# Laser_V-I_Transform.net
KiCad netlist of a schematic drawn in Altium Designer
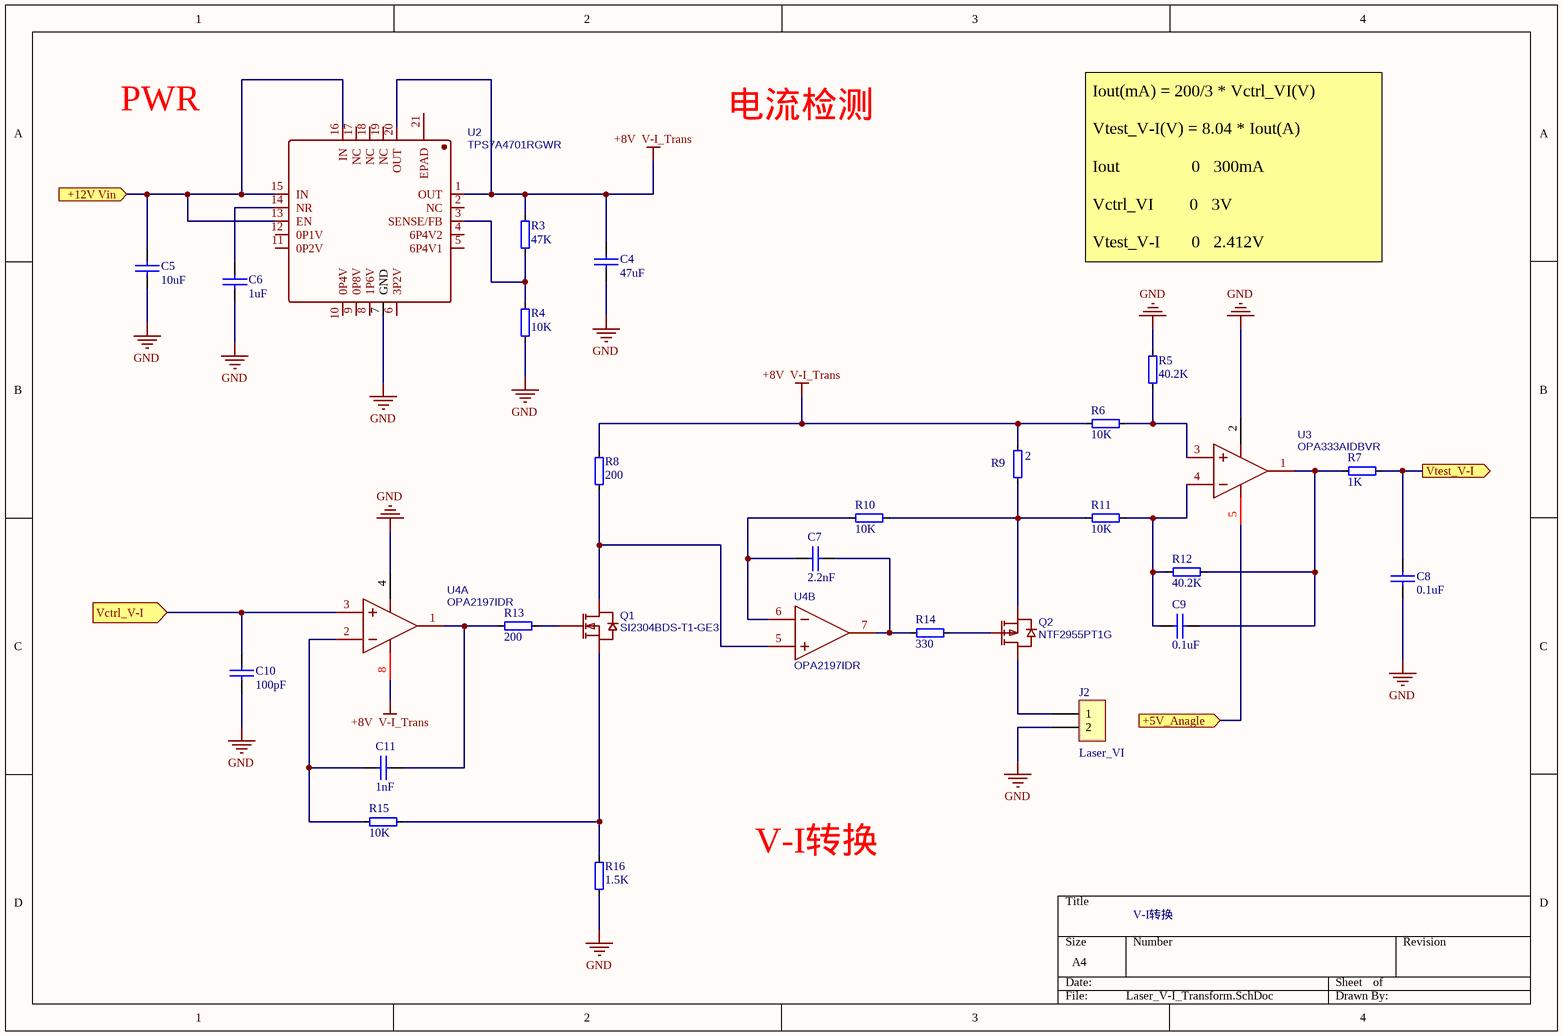
[diagram p0: Laser_V-I_Transform.SchDoc]

(export (version "E")
  (design (tool "Eeschema 10.0.6"))
  (components
    (comp (ref "C4")
      (value "47uF")
      (footprint "C 0603_M")
      (description "Capacitor")
      (libsource (lib "Laser Controller") (part "普通电容"))
    )
    (comp (ref "C5")
      (value "10uF")
      (footprint "C 0603_M")
      (description "Capacitor")
      (libsource (lib "Laser Controller") (part "普通电容"))
    )
    (comp (ref "C6")
      (value "1uF")
      (footprint "C 0603_M")
      (description "Capacitor")
      (libsource (lib "Laser Controller") (part "普通电容"))
    )
    (comp (ref "C7")
      (value "2.2nF")
      (footprint "C 0603_M")
      (description "Capacitor")
      (libsource (lib "Laser Controller") (part "普通电容"))
    )
    (comp (ref "C8")
      (value "0.1uF")
      (footprint "C 0603_M")
      (description "Capacitor")
      (libsource (lib "Laser Controller") (part "普通电容"))
    )
    (comp (ref "C9")
      (value "0.1uF")
      (footprint "C 0603_M")
      (description "Capacitor")
      (libsource (lib "Laser Controller") (part "普通电容"))
    )
    (comp (ref "C10")
      (value "100pF")
      (footprint "C 0603_M")
      (description "Capacitor")
      (libsource (lib "Laser Controller") (part "普通电容"))
    )
    (comp (ref "C11")
      (value "1nF")
      (footprint "C 0603_M")
      (description "Capacitor")
      (libsource (lib "Laser Controller") (part "普通电容"))
    )
    (comp (ref "J2")
      (value "Laser_VI")
      (footprint "KF128-5.08-2P")
      (description "jointbar")
      (libsource (lib "Laser Controller") (part "SIP2"))
    )
    (comp (ref "Q1")
      (value "SI2304BDS-T1-GE3")
      (footprint "SOT-23_L2.9-W1.3-P1.90-LS2.4-BR")
      (fields (field (name "BOM_SUPPLIER PART") "C81446"))
      (libsource (lib "Laser Controller") (part "SI2304BDS-T1-GE3"))
    )
    (comp (ref "Q2")
      (value "NTF2955PT1G")
      (footprint "SOT-223-4_L6.5-W3.5-P2.30-LS7.0-BR")
      (fields (field (name "BOM_SUPPLIER PART") "C710036") (field (name "CONTRIBUTOR") "LCSC"))
      (libsource (lib "Laser Controller") (part "NTF2955PT1G"))
    )
    (comp (ref "R3")
      (value "47K")
      (footprint "0603R")
      (description "电阻精度为0.1%")
      (libsource (lib "Laser Controller") (part "普通电阻"))
    )
    (comp (ref "R4")
      (value "10K")
      (footprint "0603R")
      (description "电阻精度为0.1%")
      (libsource (lib "Laser Controller") (part "普通电阻"))
    )
    (comp (ref "R5") (value "40.2K") (footprint "0603R") (libsource (lib "Laser Controller") (part "普通电阻")))
    (comp (ref "R6") (value "10K") (footprint "0603R") (libsource (lib "Laser Controller") (part "普通电阻")))
    (comp (ref "R7") (value "1K") (footprint "0603R") (libsource (lib "Laser Controller") (part "普通电阻")))
    (comp (ref "R8")
      (value "200")
      (footprint "0603R")
      (description "电阻精度为0.1%")
      (libsource (lib "Laser Controller") (part "普通电阻"))
    )
    (comp (ref "R9")
      (value "2")
      (footprint "0603R")
      (description "采样电阻，电阻精度为0.1%")
      (libsource (lib "Laser Controller") (part "采样电阻"))
    )
    (comp (ref "R10") (value "10K") (footprint "0603R") (libsource (lib "Laser Controller") (part "普通电阻")))
    (comp (ref "R11") (value "10K") (footprint "0603R") (libsource (lib "Laser Controller") (part "普通电阻")))
    (comp (ref "R12") (value "40.2K") (footprint "0603R") (libsource (lib "Laser Controller") (part "普通电阻")))
    (comp (ref "R13") (value "200") (footprint "0603R") (libsource (lib "Laser Controller") (part "普通电阻")))
    (comp (ref "R14") (value "330") (footprint "0603R") (libsource (lib "Laser Controller") (part "普通电阻")))
    (comp (ref "R15") (value "10K") (footprint "0603R") (libsource (lib "Laser Controller") (part "普通电阻")))
    (comp (ref "R16")
      (value "1.5K")
      (footprint "0603R")
      (description "电阻精度为0.1%")
      (libsource (lib "Laser Controller") (part "普通电阻"))
    )
    (comp (ref "U2")
      (value "TPS7A4701RGWR")
      (footprint "VQFN-20_L5.0-W5.0-P0.65-TL-EP")
      (fields (field (name "BOM_SUPPLIER PART") "C90084") (field (name "CONTRIBUTOR") "LCSC"))
      (libsource (lib "Laser Controller") (part "TPS7A4701RGWR"))
    )
    (comp (ref "U3")
      (value "OPA333AIDBVR")
      (footprint "SOT-23-5_L3.0-W1.7-P0.95-LS2.8-BR")
      (fields (field (name "BOM_SUPPLIER PART") "C30878") (field (name "CONTRIBUTOR") "LCSC"))
      (libsource (lib "Laser Controller") (part "OPA333AIDBVR"))
    )
    (comp (ref "U4")
      (value "OPA2197IDR")
      (footprint "SOIC-8_L4.9-W3.9-P1.27-LS6.0-BL")
      (fields (field (name "BOM_SUPPLIER PART") "C139363") (field (name "CONTRIBUTOR") "LCSC"))
      (libsource (lib "Laser Controller") (part "OPA2197IDR"))
    )
  )
  (nets
    (net (code "1") (name "+8V  V-I_Trans") (class "Default")
      (node (ref "C4") (pin "2") (pinfunction "2_2") (pintype "passive"))
      (node (ref "R3") (pin "2") (pinfunction "2_2") (pintype "passive"))
      (node (ref "R6") (pin "1") (pinfunction "1_1") (pintype "passive"))
      (node (ref "R8") (pin "1") (pinfunction "1_1") (pintype "passive"))
      (node (ref "R9") (pin "1") (pinfunction "1_1") (pintype "passive"))
      (node (ref "U2") (pin "1") (pinfunction "OUT_1") (pintype "passive"))
      (node (ref "U2") (pin "20") (pinfunction "OUT_20") (pintype "passive"))
      (node (ref "U4") (pin "8") (pinfunction "V+_8") (pintype "passive"))
    )
    (net (code "2") (name "/+5V_Anagle") (class "Default")
      (node (ref "U3") (pin "5") (pinfunction "V+_5") (pintype "passive"))
    )
    (net (code "3") (name "/+12V Vin") (class "Default")
      (node (ref "C5") (pin "1") (pinfunction "1_1") (pintype "passive"))
      (node (ref "U2") (pin "13") (pinfunction "EN_13") (pintype "passive"))
      (node (ref "U2") (pin "15") (pinfunction "IN_15") (pintype "passive"))
      (node (ref "U2") (pin "16") (pinfunction "IN_16") (pintype "passive"))
    )
    (net (code "4") (name "/Vctrl_V-I") (class "Default")
      (node (ref "C10") (pin "2") (pinfunction "2_2") (pintype "passive"))
      (node (ref "U4") (pin "3") (pinfunction "IN_A+_3") (pintype "passive"))
    )
    (net (code "5") (name "/Vtest_V-I") (class "Default")
      (node (ref "C8") (pin "1") (pinfunction "1_1") (pintype "passive"))
      (node (ref "R7") (pin "2") (pinfunction "2_2") (pintype "passive"))
    )
    (net (code "6") (name "GND") (class "Default")
      (node (ref "C10") (pin "1") (pinfunction "1_1") (pintype "passive"))
      (node (ref "C4") (pin "1") (pinfunction "1_1") (pintype "passive"))
      (node (ref "C5") (pin "2") (pinfunction "2_2") (pintype "passive"))
      (node (ref "C6") (pin "2") (pinfunction "2_2") (pintype "passive"))
      (node (ref "C8") (pin "2") (pinfunction "2_2") (pintype "passive"))
      (node (ref "J2") (pin "2") (pinfunction "2_2") (pintype "passive"))
      (node (ref "R16") (pin "2") (pinfunction "2_2") (pintype "passive"))
      (node (ref "R4") (pin "1") (pinfunction "1_1") (pintype "passive"))
      (node (ref "R5") (pin "2") (pinfunction "2_2") (pintype "passive"))
      (node (ref "U2") (pin "7") (pinfunction "GND_7") (pintype "passive"))
      (node (ref "U3") (pin "2") (pinfunction "V-_2") (pintype "passive"))
      (node (ref "U4") (pin "4") (pinfunction "V-_4") (pintype "passive"))
    )
    (net (code "7") (name "Net-(Q1-D)") (class "Default")
      (node (ref "Q1") (pin "3") (pinfunction "D_3") (pintype "passive"))
      (node (ref "R8") (pin "2") (pinfunction "2_2") (pintype "passive"))
      (node (ref "U4") (pin "5") (pinfunction "IN_A+_5") (pintype "passive"))
    )
    (net (code "8") (name "Net-(Q1-G)") (class "Default")
      (node (ref "Q1") (pin "1") (pinfunction "G_1") (pintype "passive"))
      (node (ref "R13") (pin "1") (pinfunction "1_1") (pintype "passive"))
    )
    (net (code "9") (name "Net-(Q1-S)") (class "Default")
      (node (ref "Q1") (pin "2") (pinfunction "S_2") (pintype "passive"))
      (node (ref "R15") (pin "1") (pinfunction "1_1") (pintype "passive"))
      (node (ref "R16") (pin "1") (pinfunction "1_1") (pintype "passive"))
    )
    (net (code "10") (name "Net-(Q2-D)") (class "Default")
      (node (ref "J2") (pin "1") (pinfunction "1_1") (pintype "passive"))
      (node (ref "Q2") (pin "2") (pinfunction "D_2") (pintype "passive"))
    )
    (net (code "11") (name "Net-(Q2-G)") (class "Default")
      (node (ref "Q2") (pin "1") (pinfunction "G_1") (pintype "passive"))
      (node (ref "R14") (pin "1") (pinfunction "1_1") (pintype "passive"))
    )
    (net (code "12") (name "Net-(Q2-S)") (class "Default")
      (node (ref "Q2") (pin "3") (pinfunction "S_3") (pintype "passive"))
      (node (ref "R10") (pin "2") (pinfunction "2_2") (pintype "passive"))
      (node (ref "R11") (pin "1") (pinfunction "1_1") (pintype "passive"))
      (node (ref "R9") (pin "2") (pinfunction "2_2") (pintype "passive"))
    )
    (net (code "13") (name "Net-(U2-NR)") (class "Default")
      (node (ref "C6") (pin "1") (pinfunction "1_1") (pintype "passive"))
      (node (ref "U2") (pin "14") (pinfunction "NR_14") (pintype "passive"))
    )
    (net (code "14") (name "Net-(U2-SENSE{slash}FB)") (class "Default")
      (node (ref "R3") (pin "1") (pinfunction "1_1") (pintype "passive"))
      (node (ref "R4") (pin "2") (pinfunction "2_2") (pintype "passive"))
      (node (ref "U2") (pin "3") (pinfunction "SENSE/FB_3") (pintype "passive"))
    )
    (net (code "15") (name "Net-(U3-IN+)") (class "Default")
      (node (ref "R5") (pin "1") (pinfunction "1_1") (pintype "passive"))
      (node (ref "R6") (pin "2") (pinfunction "2_2") (pintype "passive"))
      (node (ref "U3") (pin "3") (pinfunction "IN+_3") (pintype "passive"))
    )
    (net (code "16") (name "Net-(U3-IN-)") (class "Default")
      (node (ref "C9") (pin "2") (pinfunction "2_2") (pintype "passive"))
      (node (ref "R11") (pin "2") (pinfunction "2_2") (pintype "passive"))
      (node (ref "R12") (pin "1") (pinfunction "1_1") (pintype "passive"))
      (node (ref "U3") (pin "4") (pinfunction "IN-_4") (pintype "passive"))
    )
    (net (code "17") (name "Net-(U3-OUT)") (class "Default")
      (node (ref "C9") (pin "1") (pinfunction "1_1") (pintype "passive"))
      (node (ref "R12") (pin "2") (pinfunction "2_2") (pintype "passive"))
      (node (ref "R7") (pin "1") (pinfunction "1_1") (pintype "passive"))
      (node (ref "U3") (pin "1") (pinfunction "OUT_1") (pintype "passive"))
    )
    (net (code "18") (name "Net-(U4A-IN_A-)") (class "Default")
      (node (ref "C11") (pin "2") (pinfunction "2_2") (pintype "passive"))
      (node (ref "R15") (pin "2") (pinfunction "2_2") (pintype "passive"))
      (node (ref "U4") (pin "2") (pinfunction "IN_A-_2") (pintype "passive"))
    )
    (net (code "19") (name "Net-(U4A-OUT_A)") (class "Default")
      (node (ref "C11") (pin "1") (pinfunction "1_1") (pintype "passive"))
      (node (ref "R13") (pin "2") (pinfunction "2_2") (pintype "passive"))
      (node (ref "U4") (pin "1") (pinfunction "OUT_A_1") (pintype "passive"))
    )
    (net (code "20") (name "Net-(U4B-IN_A-)") (class "Default")
      (node (ref "C7") (pin "2") (pinfunction "2_2") (pintype "passive"))
      (node (ref "R10") (pin "1") (pinfunction "1_1") (pintype "passive"))
      (node (ref "U4") (pin "6") (pinfunction "IN_A-_6") (pintype "passive"))
    )
    (net (code "21") (name "Net-(U4B-OUT_A)") (class "Default")
      (node (ref "C7") (pin "1") (pinfunction "1_1") (pintype "passive"))
      (node (ref "R14") (pin "2") (pinfunction "2_2") (pintype "passive"))
      (node (ref "U4") (pin "7") (pinfunction "OUT_A_7") (pintype "passive"))
    )
    (net (code "22") (name "unconnected-(U2-0P1V-Pad12)") (class "Default")
      (node (ref "U2") (pin "12") (pinfunction "0P1V_12") (pintype "passive"))
    )
    (net (code "23") (name "unconnected-(U2-0P2V-Pad11)") (class "Default")
      (node (ref "U2") (pin "11") (pinfunction "0P2V_11") (pintype "passive"))
    )
    (net (code "24") (name "unconnected-(U2-0P4V-Pad10)") (class "Default")
      (node (ref "U2") (pin "10") (pinfunction "0P4V_10") (pintype "passive"))
    )
    (net (code "25") (name "unconnected-(U2-0P8V-Pad9)") (class "Default")
      (node (ref "U2") (pin "9") (pinfunction "0P8V_9") (pintype "passive"))
    )
    (net (code "26") (name "unconnected-(U2-1P6V-Pad8)") (class "Default")
      (node (ref "U2") (pin "8") (pinfunction "1P6V_8") (pintype "passive"))
    )
    (net (code "27") (name "unconnected-(U2-3P2V-Pad6)") (class "Default")
      (node (ref "U2") (pin "6") (pinfunction "3P2V_6") (pintype "passive"))
    )
    (net (code "28") (name "unconnected-(U2-6P4V1-Pad5)") (class "Default")
      (node (ref "U2") (pin "5") (pinfunction "6P4V1_5") (pintype "passive"))
    )
    (net (code "29") (name "unconnected-(U2-6P4V2-Pad4)") (class "Default")
      (node (ref "U2") (pin "4") (pinfunction "6P4V2_4") (pintype "passive"))
    )
    (net (code "30") (name "unconnected-(U2-EPAD-Pad21)") (class "Default")
      (node (ref "U2") (pin "21") (pinfunction "EPAD_21") (pintype "passive"))
    )
    (net (code "31") (name "unconnected-(U2-NC-Pad2)") (class "Default")
      (node (ref "U2") (pin "2") (pinfunction "NC_2") (pintype "passive"))
    )
    (net (code "32") (name "unconnected-(U2-NC-Pad17)") (class "Default")
      (node (ref "U2") (pin "17") (pinfunction "NC_17") (pintype "passive"))
    )
    (net (code "33") (name "unconnected-(U2-NC-Pad18)") (class "Default")
      (node (ref "U2") (pin "18") (pinfunction "NC_18") (pintype "passive"))
    )
    (net (code "34") (name "unconnected-(U2-NC-Pad19)") (class "Default")
      (node (ref "U2") (pin "19") (pinfunction "NC_19") (pintype "passive"))
    )
  )
)
